# schematic1.net
KiCad netlist of a schematic drawn in EAGLE
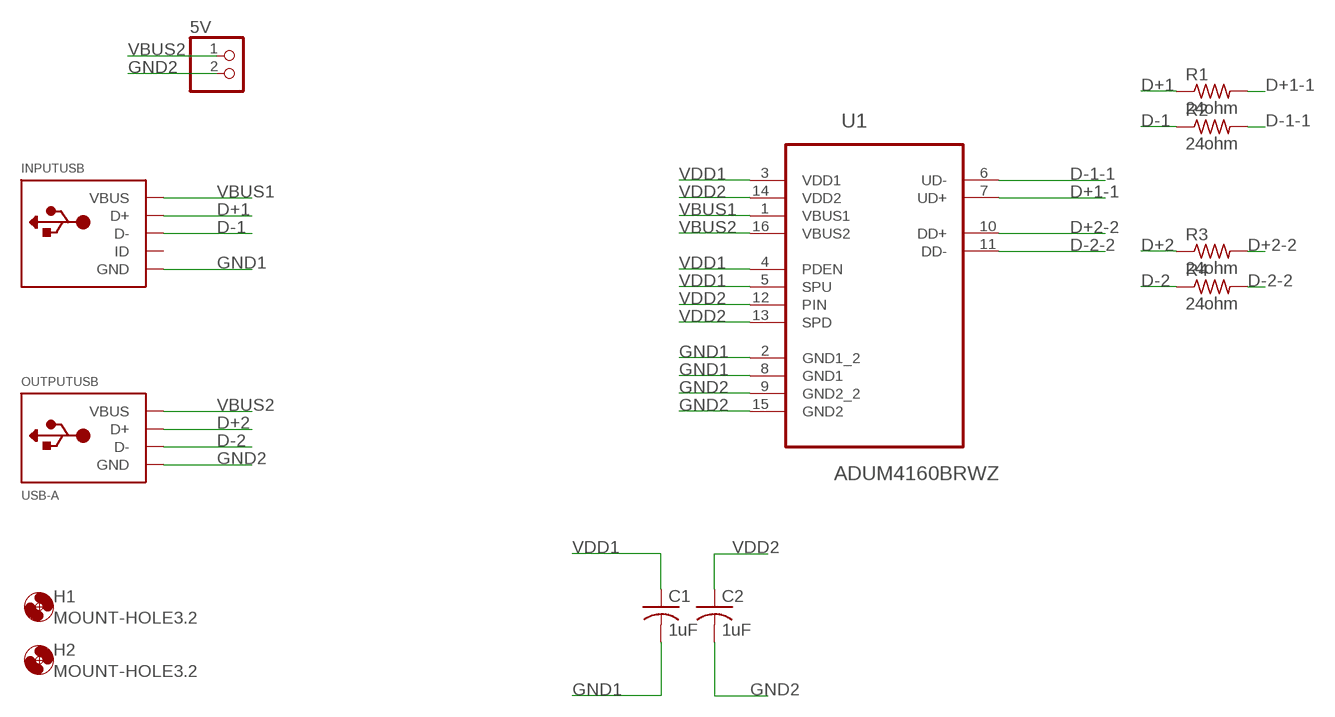
[diagram p0: schematic, sheet 1]

(export (version "E")
  (design (tool "Eeschema 10.0.6"))
  (components
    (comp (ref "5V")
      (value "PINHD-1X2")
      (footprint "eagle-import:1X02")
      (libsource (lib "eagle-import") (part "PINHD-1X2"))
    )
    (comp (ref "C1")
      (value "1uF")
      (footprint "eagle-import:C0805")
      (libsource (lib "eagle-import") (part "C-USC0805"))
    )
    (comp (ref "C2")
      (value "1uF")
      (footprint "eagle-import:C0805")
      (libsource (lib "eagle-import") (part "C-USC0805"))
    )
    (comp (ref "H1")
      (value "MOUNT-HOLE3.2")
      (footprint "eagle-import:3,2")
      (libsource (lib "eagle-import") (part "MOUNT-HOLE3.2"))
    )
    (comp (ref "H2")
      (value "MOUNT-HOLE3.2")
      (footprint "eagle-import:3,2")
      (libsource (lib "eagle-import") (part "MOUNT-HOLE3.2"))
    )
    (comp (ref "INPUTUSB")
      (value "USBMINIB")
      (footprint "eagle-import:USB-MINIB")
      (libsource (lib "eagle-import") (part "USBMINIB"))
    )
    (comp (ref "OUTPUTUSB")
      (value "USB-A")
      (footprint "eagle-import:MOLEX_480371000")
      (libsource (lib "eagle-import") (part "USB-A"))
    )
    (comp (ref "R1")
      (value "24ohm")
      (footprint "eagle-import:R0805")
      (libsource (lib "eagle-import") (part "R-US_R0805"))
    )
    (comp (ref "R2")
      (value "24ohm")
      (footprint "eagle-import:R0805")
      (libsource (lib "eagle-import") (part "R-US_R0805"))
    )
    (comp (ref "R3")
      (value "24ohm")
      (footprint "eagle-import:R0805")
      (libsource (lib "eagle-import") (part "R-US_R0805"))
    )
    (comp (ref "R4")
      (value "24ohm")
      (footprint "eagle-import:R0805")
      (libsource (lib "eagle-import") (part "R-US_R0805"))
    )
    (comp (ref "U1")
      (value "ADUM4160BRWZ")
      (footprint "eagle-import:SOIC127P1032X265-16N")
      (libsource (lib "eagle-import") (part "ADUM4160BRWZ"))
    )
  )
  (nets
    (net (code "1") (name "/D+1") (class "Default")
      (node (ref "INPUTUSB") (pin "D+") (pinfunction "D+_D+") (pintype "bidirectional"))
      (node (ref "R1") (pin "1") (pinfunction "1_1") (pintype "passive"))
    )
    (net (code "2") (name "/D+1-1") (class "Default")
      (node (ref "R1") (pin "2") (pinfunction "2_2") (pintype "passive"))
      (node (ref "U1") (pin "7") (pinfunction "UD+_7") (pintype "bidirectional"))
    )
    (net (code "3") (name "/D+2") (class "Default")
      (node (ref "OUTPUTUSB") (pin "3") (pinfunction "D+_3") (pintype "bidirectional"))
      (node (ref "R3") (pin "1") (pinfunction "1_1") (pintype "passive"))
    )
    (net (code "4") (name "/D+2-2") (class "Default")
      (node (ref "R3") (pin "2") (pinfunction "2_2") (pintype "passive"))
      (node (ref "U1") (pin "10") (pinfunction "DD+_10") (pintype "bidirectional"))
    )
    (net (code "5") (name "/D-1") (class "Default")
      (node (ref "INPUTUSB") (pin "D-") (pinfunction "D-_D-") (pintype "bidirectional"))
      (node (ref "R2") (pin "1") (pinfunction "1_1") (pintype "passive"))
    )
    (net (code "6") (name "/D-1-1") (class "Default")
      (node (ref "R2") (pin "2") (pinfunction "2_2") (pintype "passive"))
      (node (ref "U1") (pin "6") (pinfunction "UD-_6") (pintype "bidirectional"))
    )
    (net (code "7") (name "/D-2") (class "Default")
      (node (ref "OUTPUTUSB") (pin "2") (pinfunction "D-_2") (pintype "bidirectional"))
      (node (ref "R4") (pin "1") (pinfunction "1_1") (pintype "passive"))
    )
    (net (code "8") (name "/D-2-2") (class "Default")
      (node (ref "R4") (pin "2") (pinfunction "2_2") (pintype "passive"))
      (node (ref "U1") (pin "11") (pinfunction "DD-_11") (pintype "bidirectional"))
    )
    (net (code "9") (name "/GND1") (class "Default")
      (node (ref "C1") (pin "2") (pinfunction "2_2") (pintype "passive"))
      (node (ref "INPUTUSB") (pin "GND") (pinfunction "GND_GND") (pintype "power_in"))
      (node (ref "U1") (pin "2") (pinfunction "GND1_2_2") (pintype "passive"))
      (node (ref "U1") (pin "8") (pinfunction "GND1_8") (pintype "passive"))
    )
    (net (code "10") (name "/GND2") (class "Default")
      (node (ref "5V") (pin "2") (pinfunction "2_2") (pintype "passive"))
      (node (ref "C2") (pin "2") (pinfunction "2_2") (pintype "passive"))
      (node (ref "OUTPUTUSB") (pin "4") (pinfunction "GND_4") (pintype "power_in"))
      (node (ref "U1") (pin "15") (pinfunction "GND2_15") (pintype "passive"))
      (node (ref "U1") (pin "9") (pinfunction "GND2_2_9") (pintype "passive"))
    )
    (net (code "11") (name "/VBUS1") (class "Default")
      (node (ref "INPUTUSB") (pin "VBUS") (pinfunction "VBUS_VBUS") (pintype "power_in"))
      (node (ref "U1") (pin "1") (pinfunction "VBUS1_1") (pintype "power_in"))
    )
    (net (code "12") (name "/VBUS2") (class "Default")
      (node (ref "5V") (pin "1") (pinfunction "1_1") (pintype "passive"))
      (node (ref "OUTPUTUSB") (pin "1") (pinfunction "VBUS_1") (pintype "power_in"))
      (node (ref "U1") (pin "16") (pinfunction "VBUS2_16") (pintype "power_in"))
    )
    (net (code "13") (name "/VDD1") (class "Default")
      (node (ref "C1") (pin "1") (pinfunction "1_1") (pintype "passive"))
      (node (ref "U1") (pin "3") (pinfunction "VDD1_3") (pintype "power_in"))
      (node (ref "U1") (pin "4") (pinfunction "PDEN_4") (pintype "input"))
      (node (ref "U1") (pin "5") (pinfunction "SPU_5") (pintype "input"))
    )
    (net (code "14") (name "/VDD2") (class "Default")
      (node (ref "C2") (pin "1") (pinfunction "1_1") (pintype "passive"))
      (node (ref "U1") (pin "12") (pinfunction "PIN_12") (pintype "input"))
      (node (ref "U1") (pin "13") (pinfunction "SPD_13") (pintype "input"))
      (node (ref "U1") (pin "14") (pinfunction "VDD2_14") (pintype "power_in"))
    )
    (net (code "15") (name "unconnected-(INPUTUSB-PadID)") (class "Default")
      (node (ref "INPUTUSB") (pin "ID") (pinfunction "ID_ID") (pintype "bidirectional"))
    )
  )
)
